# DM3370_speaker.net
KiCad netlist of a schematic drawn in Altium Designer
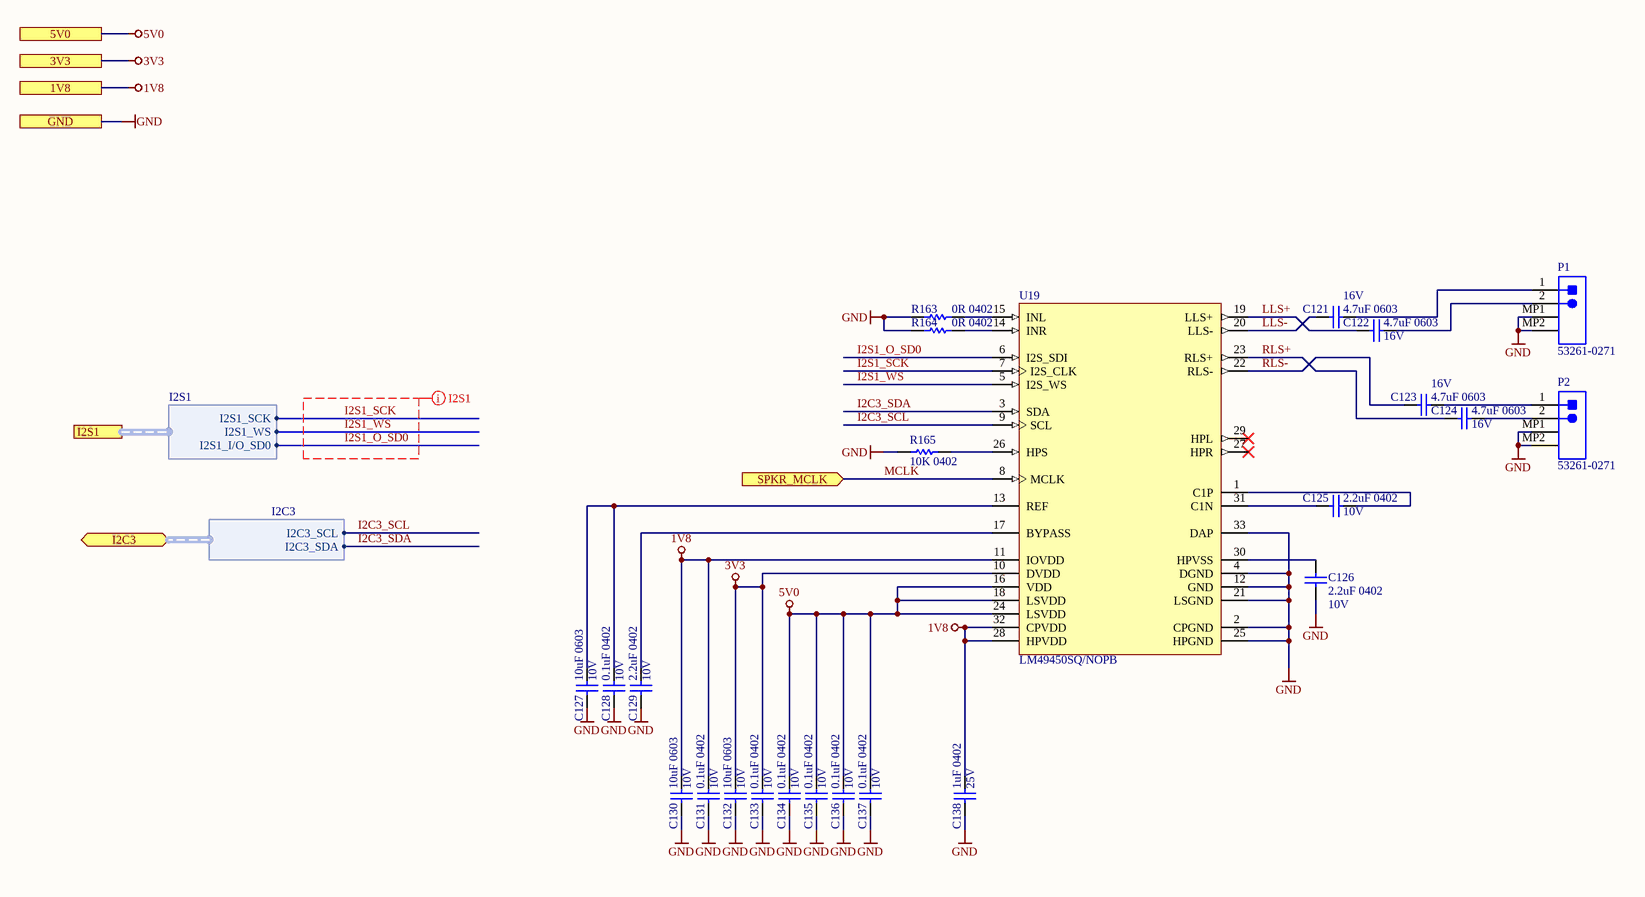
[diagram p0: DM3370_speaker.SchDoc]

(export (version "E")
  (design (tool "Eeschema 10.0.6"))
  (components
    (comp (ref "C121")
      (value "4.7uF 0603")
      (footprint "CAP_Altium_Vault_Generic:CAPC0603(1608)100_L")
      (description "CAP CER 4.7UF 16V X5R 0603 10%")
      (fields (field (name "TOLERANCE") "10%") (field (name "VOLTAGE RATING") "16V"))
      (libsource (lib "LuxonisMaster") (part "GRM188R61C475KAAJD"))
    )
    (comp (ref "C122")
      (value "4.7uF 0603")
      (footprint "CAP_Altium_Vault_Generic:CAPC0603(1608)100_L")
      (description "CAP CER 4.7UF 16V X5R 0603 10%")
      (fields (field (name "TOLERANCE") "10%") (field (name "VOLTAGE RATING") "16V"))
      (libsource (lib "LuxonisMaster") (part "GRM188R61C475KAAJD"))
    )
    (comp (ref "C123")
      (value "4.7uF 0603")
      (footprint "CAP_Altium_Vault_Generic:CAPC0603(1608)100_L")
      (description "CAP CER 4.7UF 16V X5R 0603 10%")
      (fields (field (name "TOLERANCE") "10%") (field (name "VOLTAGE RATING") "16V"))
      (libsource (lib "LuxonisMaster") (part "GRM188R61C475KAAJD"))
    )
    (comp (ref "C124")
      (value "4.7uF 0603")
      (footprint "CAP_Altium_Vault_Generic:CAPC0603(1608)100_L")
      (description "CAP CER 4.7UF 16V X5R 0603 10%")
      (fields (field (name "TOLERANCE") "10%") (field (name "VOLTAGE RATING") "16V"))
      (libsource (lib "LuxonisMaster") (part "GRM188R61C475KAAJD"))
    )
    (comp (ref "C125")
      (value "2.2uF 0402")
      (footprint "CAP_Altium_Vault_Generic:CAPC0402(1005)70_L")
      (description "CAP CER 2.2UF 10V X5R 0402 10%")
      (fields (field (name "TOLERANCE") "10%") (field (name "VOLTAGE RATING") "10V"))
      (libsource (lib "LuxonisMaster") (part "GRM155R61A225KE95D"))
    )
    (comp (ref "C126")
      (value "2.2uF 0402")
      (footprint "CAP_Altium_Vault_Generic:CAPC0402(1005)70_L")
      (description "CAP CER 2.2UF 10V X5R 0402 10%")
      (fields (field (name "TOLERANCE") "10%") (field (name "VOLTAGE RATING") "10V"))
      (libsource (lib "LuxonisMaster") (part "GRM155R61A225KE95D"))
    )
    (comp (ref "C127")
      (value "10uF 0603")
      (footprint "CAP_Altium_Vault_Generic:CAPC0603(1608)100_L")
      (description "CAP CER 10UF 10V X5R 0603 20%")
      (fields (field (name "TOLERANCE") "20%") (field (name "VOLTAGE RATING") "10V"))
      (libsource (lib "LuxonisMaster") (part "GRM188R61A106ME69D"))
    )
    (comp (ref "C128")
      (value "0.1uF 0402")
      (footprint "CAP_Altium_Vault_Generic:CAPC0402(1005)70_L")
      (description "CAP CER 0.1UF 10V X7R 0402 5%")
      (fields (field (name "TOLERANCE") "5%") (field (name "VOLTAGE RATING") "10V"))
      (libsource (lib "LuxonisMaster") (part "GRM155R71A104JA01D"))
    )
    (comp (ref "C129")
      (value "2.2uF 0402")
      (footprint "CAP_Altium_Vault_Generic:CAPC0402(1005)70_L")
      (description "CAP CER 2.2UF 10V X5R 0402 10%")
      (fields (field (name "TOLERANCE") "10%") (field (name "VOLTAGE RATING") "10V"))
      (libsource (lib "LuxonisMaster") (part "GRM155R61A225KE95D"))
    )
    (comp (ref "C130")
      (value "10uF 0603")
      (footprint "CAP_Altium_Vault_Generic:CAPC0603(1608)100_L")
      (description "CAP CER 10UF 10V X5R 0603 20%")
      (fields (field (name "TOLERANCE") "20%") (field (name "VOLTAGE RATING") "10V"))
      (libsource (lib "LuxonisMaster") (part "GRM188R61A106ME69D"))
    )
    (comp (ref "C131")
      (value "0.1uF 0402")
      (footprint "CAP_Altium_Vault_Generic:CAPC0402(1005)70_L")
      (description "CAP CER 0.1UF 10V X7R 0402 5%")
      (fields (field (name "TOLERANCE") "5%") (field (name "VOLTAGE RATING") "10V"))
      (libsource (lib "LuxonisMaster") (part "GRM155R71A104JA01D"))
    )
    (comp (ref "C132")
      (value "10uF 0603")
      (footprint "CAP_Altium_Vault_Generic:CAPC0603(1608)100_L")
      (description "CAP CER 10UF 10V X5R 0603 20%")
      (fields (field (name "TOLERANCE") "20%") (field (name "VOLTAGE RATING") "10V"))
      (libsource (lib "LuxonisMaster") (part "GRM188R61A106ME69D"))
    )
    (comp (ref "C133")
      (value "0.1uF 0402")
      (footprint "CAP_Altium_Vault_Generic:CAPC0402(1005)70_L")
      (description "CAP CER 0.1UF 10V X7R 0402 5%")
      (fields (field (name "TOLERANCE") "5%") (field (name "VOLTAGE RATING") "10V"))
      (libsource (lib "LuxonisMaster") (part "GRM155R71A104JA01D"))
    )
    (comp (ref "C134")
      (value "0.1uF 0402")
      (footprint "CAP_Altium_Vault_Generic:CAPC0402(1005)70_L")
      (description "CAP CER 0.1UF 10V X7R 0402 5%")
      (fields (field (name "TOLERANCE") "5%") (field (name "VOLTAGE RATING") "10V"))
      (libsource (lib "LuxonisMaster") (part "GRM155R71A104JA01D"))
    )
    (comp (ref "C135")
      (value "0.1uF 0402")
      (footprint "CAP_Altium_Vault_Generic:CAPC0402(1005)70_L")
      (description "CAP CER 0.1UF 10V X7R 0402 5%")
      (fields (field (name "TOLERANCE") "5%") (field (name "VOLTAGE RATING") "10V"))
      (libsource (lib "LuxonisMaster") (part "GRM155R71A104JA01D"))
    )
    (comp (ref "C136")
      (value "0.1uF 0402")
      (footprint "CAP_Altium_Vault_Generic:CAPC0402(1005)70_L")
      (description "CAP CER 0.1UF 10V X7R 0402 5%")
      (fields (field (name "TOLERANCE") "5%") (field (name "VOLTAGE RATING") "10V"))
      (libsource (lib "LuxonisMaster") (part "GRM155R71A104JA01D"))
    )
    (comp (ref "C137")
      (value "0.1uF 0402")
      (footprint "CAP_Altium_Vault_Generic:CAPC0402(1005)70_L")
      (description "CAP CER 0.1UF 10V X7R 0402 5%")
      (fields (field (name "TOLERANCE") "5%") (field (name "VOLTAGE RATING") "10V"))
      (libsource (lib "LuxonisMaster") (part "GRM155R71A104JA01D"))
    )
    (comp (ref "C138")
      (value "1uF 0402")
      (footprint "CAP_Altium_Vault_Generic:CAPC0402(1005)70_L")
      (description "CAP CER 1UF 25V X5R 0402 10%")
      (fields
        (field (name "TOLERANCE") "10%")
        (field (name "VOLTAGE") "25V")
        (field (name "VOLTAGE RATING") "25V")
      )
      (libsource (lib "LuxonisMaster") (part "GRM155R61E105KA12D"))
    )
    (comp (ref "P1")
      (value "53261-0271")
      (footprint "MOLX-53261-0271_V")
      (libsource (lib "Luxonis LLC") (part "CN-1P-2M-R2"))
    )
    (comp (ref "P2")
      (value "53261-0271")
      (footprint "MOLX-53261-0271_V")
      (libsource (lib "Luxonis LLC") (part "CN-1P-2M-R2"))
    )
    (comp (ref "R163")
      (value "0R 0402")
      (footprint "RES_Altium_Vault_Generic:RESC0402(1005)_L")
      (description "RES SMD 0 OHM JUMPER 1/16W 0402")
      (fields (field (name "TOLERANCE") "5%"))
      (libsource (lib "LuxonisMaster") (part "CRCW04020000Z0ED"))
    )
    (comp (ref "R164")
      (value "0R 0402")
      (footprint "RES_Altium_Vault_Generic:RESC0402(1005)_L")
      (description "RES SMD 0 OHM JUMPER 1/16W 0402")
      (fields (field (name "TOLERANCE") "5%"))
      (libsource (lib "LuxonisMaster") (part "CRCW04020000Z0ED"))
    )
    (comp (ref "R165")
      (value "10K 0402")
      (footprint "RES_Altium_Vault_Generic:RESC0402(1005)_L")
      (fields (field (name "TOLERANCE") "1%"))
      (libsource (lib "LuxonisMaster") (part "RC0402FR-1310KL"))
    )
    (comp (ref "U19")
      (value "LM49450SQ/NOPB")
      (footprint "QFN50P500X500X80_HS-33N")
      (libsource (lib "Luxonis LLC") (part "LM49450SQ/NOPB"))
    )
  )
  (nets
    (net (code "3") (name "/I2C3_SCL") (class "Default")
      (node (ref "U19") (pin "9") (pinfunction "SCL_9") (pintype "input"))
    )
    (net (code "4") (name "/I2C3_SDA") (class "Default")
      (node (ref "U19") (pin "3") (pinfunction "SDA_3") (pintype "input"))
    )
    (net (code "5") (name "/I2S1_O_SD0") (class "Default")
      (node (ref "U19") (pin "6") (pinfunction "I2S_SDI_6") (pintype "input"))
    )
    (net (code "6") (name "/I2S1_SCK") (class "Default")
      (node (ref "U19") (pin "7") (pinfunction "I2S_CLK_7") (pintype "input"))
    )
    (net (code "7") (name "/I2S1_WS") (class "Default")
      (node (ref "U19") (pin "5") (pinfunction "I2S_WS_5") (pintype "input"))
    )
    (net (code "8") (name "/LLS+") (class "Default")
      (node (ref "C122") (pin "1") (pinfunction "1_1") (pintype "passive"))
      (node (ref "U19") (pin "19") (pinfunction "LLS+_19") (pintype "output"))
    )
    (net (code "9") (name "/LLS-") (class "Default")
      (node (ref "C121") (pin "1") (pinfunction "1_1") (pintype "passive"))
      (node (ref "U19") (pin "20") (pinfunction "LLS-_20") (pintype "output"))
    )
    (net (code "10") (name "/MCLK") (class "Default")
      (node (ref "U19") (pin "8") (pinfunction "MCLK_8") (pintype "input"))
    )
    (net (code "11") (name "/RLS+") (class "Default")
      (node (ref "C124") (pin "1") (pinfunction "1_1") (pintype "passive"))
      (node (ref "U19") (pin "23") (pinfunction "RLS+_23") (pintype "output"))
    )
    (net (code "12") (name "/RLS-") (class "Default")
      (node (ref "C123") (pin "1") (pinfunction "1_1") (pintype "passive"))
      (node (ref "U19") (pin "22") (pinfunction "RLS-_22") (pintype "output"))
    )
    (net (code "15") (name "1V8") (class "Default")
      (node (ref "C130") (pin "2") (pinfunction "2_2") (pintype "passive"))
      (node (ref "C131") (pin "2") (pinfunction "2_2") (pintype "passive"))
      (node (ref "C138") (pin "2") (pinfunction "2_2") (pintype "passive"))
      (node (ref "U19") (pin "11") (pinfunction "IOVDD_11") (pintype "power_in"))
      (node (ref "U19") (pin "28") (pinfunction "HPVDD_28") (pintype "power_in"))
      (node (ref "U19") (pin "32") (pinfunction "CPVDD_32") (pintype "power_in"))
    )
    (net (code "16") (name "3V3") (class "Default")
      (node (ref "C132") (pin "2") (pinfunction "2_2") (pintype "passive"))
      (node (ref "C133") (pin "2") (pinfunction "2_2") (pintype "passive"))
      (node (ref "U19") (pin "10") (pinfunction "DVDD_10") (pintype "power_in"))
    )
    (net (code "17") (name "5V0") (class "Default")
      (node (ref "C134") (pin "2") (pinfunction "2_2") (pintype "passive"))
      (node (ref "C135") (pin "2") (pinfunction "2_2") (pintype "passive"))
      (node (ref "C136") (pin "2") (pinfunction "2_2") (pintype "passive"))
      (node (ref "C137") (pin "2") (pinfunction "2_2") (pintype "passive"))
      (node (ref "U19") (pin "16") (pinfunction "VDD_16") (pintype "power_in"))
      (node (ref "U19") (pin "18") (pinfunction "LSVDD_18") (pintype "power_in"))
      (node (ref "U19") (pin "24") (pinfunction "LSVDD_24") (pintype "power_in"))
    )
    (net (code "18") (name "GND") (class "Default")
      (node (ref "C126") (pin "1") (pinfunction "1_1") (pintype "passive"))
      (node (ref "C127") (pin "1") (pinfunction "1_1") (pintype "passive"))
      (node (ref "C128") (pin "1") (pinfunction "1_1") (pintype "passive"))
      (node (ref "C129") (pin "1") (pinfunction "1_1") (pintype "passive"))
      (node (ref "C130") (pin "1") (pinfunction "1_1") (pintype "passive"))
      (node (ref "C131") (pin "1") (pinfunction "1_1") (pintype "passive"))
      (node (ref "C132") (pin "1") (pinfunction "1_1") (pintype "passive"))
      (node (ref "C133") (pin "1") (pinfunction "1_1") (pintype "passive"))
      (node (ref "C134") (pin "1") (pinfunction "1_1") (pintype "passive"))
      (node (ref "C135") (pin "1") (pinfunction "1_1") (pintype "passive"))
      (node (ref "C136") (pin "1") (pinfunction "1_1") (pintype "passive"))
      (node (ref "C137") (pin "1") (pinfunction "1_1") (pintype "passive"))
      (node (ref "C138") (pin "1") (pinfunction "1_1") (pintype "passive"))
      (node (ref "P1") (pin "MP1") (pinfunction "MP1_MP1") (pintype "passive"))
      (node (ref "P1") (pin "MP2") (pinfunction "MP2_MP2") (pintype "passive"))
      (node (ref "P2") (pin "MP1") (pinfunction "MP1_MP1") (pintype "passive"))
      (node (ref "P2") (pin "MP2") (pinfunction "MP2_MP2") (pintype "passive"))
      (node (ref "R163") (pin "1") (pinfunction "1_1") (pintype "passive"))
      (node (ref "R164") (pin "1") (pinfunction "1_1") (pintype "passive"))
      (node (ref "R165") (pin "1") (pinfunction "1_1") (pintype "passive"))
      (node (ref "U19") (pin "12") (pinfunction "GND_12") (pintype "power_in"))
      (node (ref "U19") (pin "2") (pinfunction "CPGND_2") (pintype "power_in"))
      (node (ref "U19") (pin "21") (pinfunction "LSGND_21") (pintype "power_in"))
      (node (ref "U19") (pin "25") (pinfunction "HPGND_25") (pintype "power_in"))
      (node (ref "U19") (pin "33") (pinfunction "DAP_33") (pintype "power_in"))
      (node (ref "U19") (pin "4") (pinfunction "DGND_4") (pintype "power_in"))
    )
    (net (code "19") (name "Net-(C121-Pad2)") (class "Default")
      (node (ref "C121") (pin "2") (pinfunction "2_2") (pintype "passive"))
      (node (ref "P1") (pin "1") (pinfunction "1_1") (pintype "passive"))
    )
    (net (code "20") (name "Net-(C122-Pad2)") (class "Default")
      (node (ref "C122") (pin "2") (pinfunction "2_2") (pintype "passive"))
      (node (ref "P1") (pin "2") (pinfunction "2_2") (pintype "passive"))
    )
    (net (code "21") (name "Net-(C123-Pad2)") (class "Default")
      (node (ref "C123") (pin "2") (pinfunction "2_2") (pintype "passive"))
      (node (ref "P2") (pin "1") (pinfunction "1_1") (pintype "passive"))
    )
    (net (code "22") (name "Net-(C124-Pad2)") (class "Default")
      (node (ref "C124") (pin "2") (pinfunction "2_2") (pintype "passive"))
      (node (ref "P2") (pin "2") (pinfunction "2_2") (pintype "passive"))
    )
    (net (code "23") (name "Net-(U19-BYPASS)") (class "Default")
      (node (ref "C129") (pin "2") (pinfunction "2_2") (pintype "passive"))
      (node (ref "U19") (pin "17") (pinfunction "BYPASS_17") (pintype "passive"))
    )
    (net (code "24") (name "Net-(U19-C1N)") (class "Default")
      (node (ref "C125") (pin "2") (pinfunction "2_2") (pintype "passive"))
      (node (ref "U19") (pin "31") (pinfunction "C1N_31") (pintype "passive"))
    )
    (net (code "25") (name "Net-(U19-C1P)") (class "Default")
      (node (ref "C125") (pin "1") (pinfunction "1_1") (pintype "passive"))
      (node (ref "U19") (pin "1") (pinfunction "C1P_1") (pintype "passive"))
    )
    (net (code "26") (name "Net-(U19-HPS)") (class "Default")
      (node (ref "R165") (pin "2") (pinfunction "2_2") (pintype "passive"))
      (node (ref "U19") (pin "26") (pinfunction "HPS_26") (pintype "input"))
    )
    (net (code "27") (name "Net-(U19-HPVSS)") (class "Default")
      (node (ref "C126") (pin "2") (pinfunction "2_2") (pintype "passive"))
      (node (ref "U19") (pin "30") (pinfunction "HPVSS_30") (pintype "power_in"))
    )
    (net (code "28") (name "Net-(U19-INL)") (class "Default")
      (node (ref "R163") (pin "2") (pinfunction "2_2") (pintype "passive"))
      (node (ref "U19") (pin "15") (pinfunction "INL_15") (pintype "input"))
    )
    (net (code "29") (name "Net-(U19-INR)") (class "Default")
      (node (ref "R164") (pin "2") (pinfunction "2_2") (pintype "passive"))
      (node (ref "U19") (pin "14") (pinfunction "INR_14") (pintype "input"))
    )
    (net (code "30") (name "Net-(U19-REF)") (class "Default")
      (node (ref "C127") (pin "2") (pinfunction "2_2") (pintype "passive"))
      (node (ref "C128") (pin "2") (pinfunction "2_2") (pintype "passive"))
      (node (ref "U19") (pin "13") (pinfunction "REF_13") (pintype "passive"))
    )
    (net (code "31") (name "unconnected-(U19-HPL-Pad29)") (class "Default")
      (node (ref "U19") (pin "29") (pinfunction "HPL_29") (pintype "output+no_connect"))
    )
    (net (code "32") (name "unconnected-(U19-HPR-Pad27)") (class "Default")
      (node (ref "U19") (pin "27") (pinfunction "HPR_27") (pintype "output+no_connect"))
    )
  )
)
